# PR9018.net
KiCad netlist of a schematic drawn in EAGLE
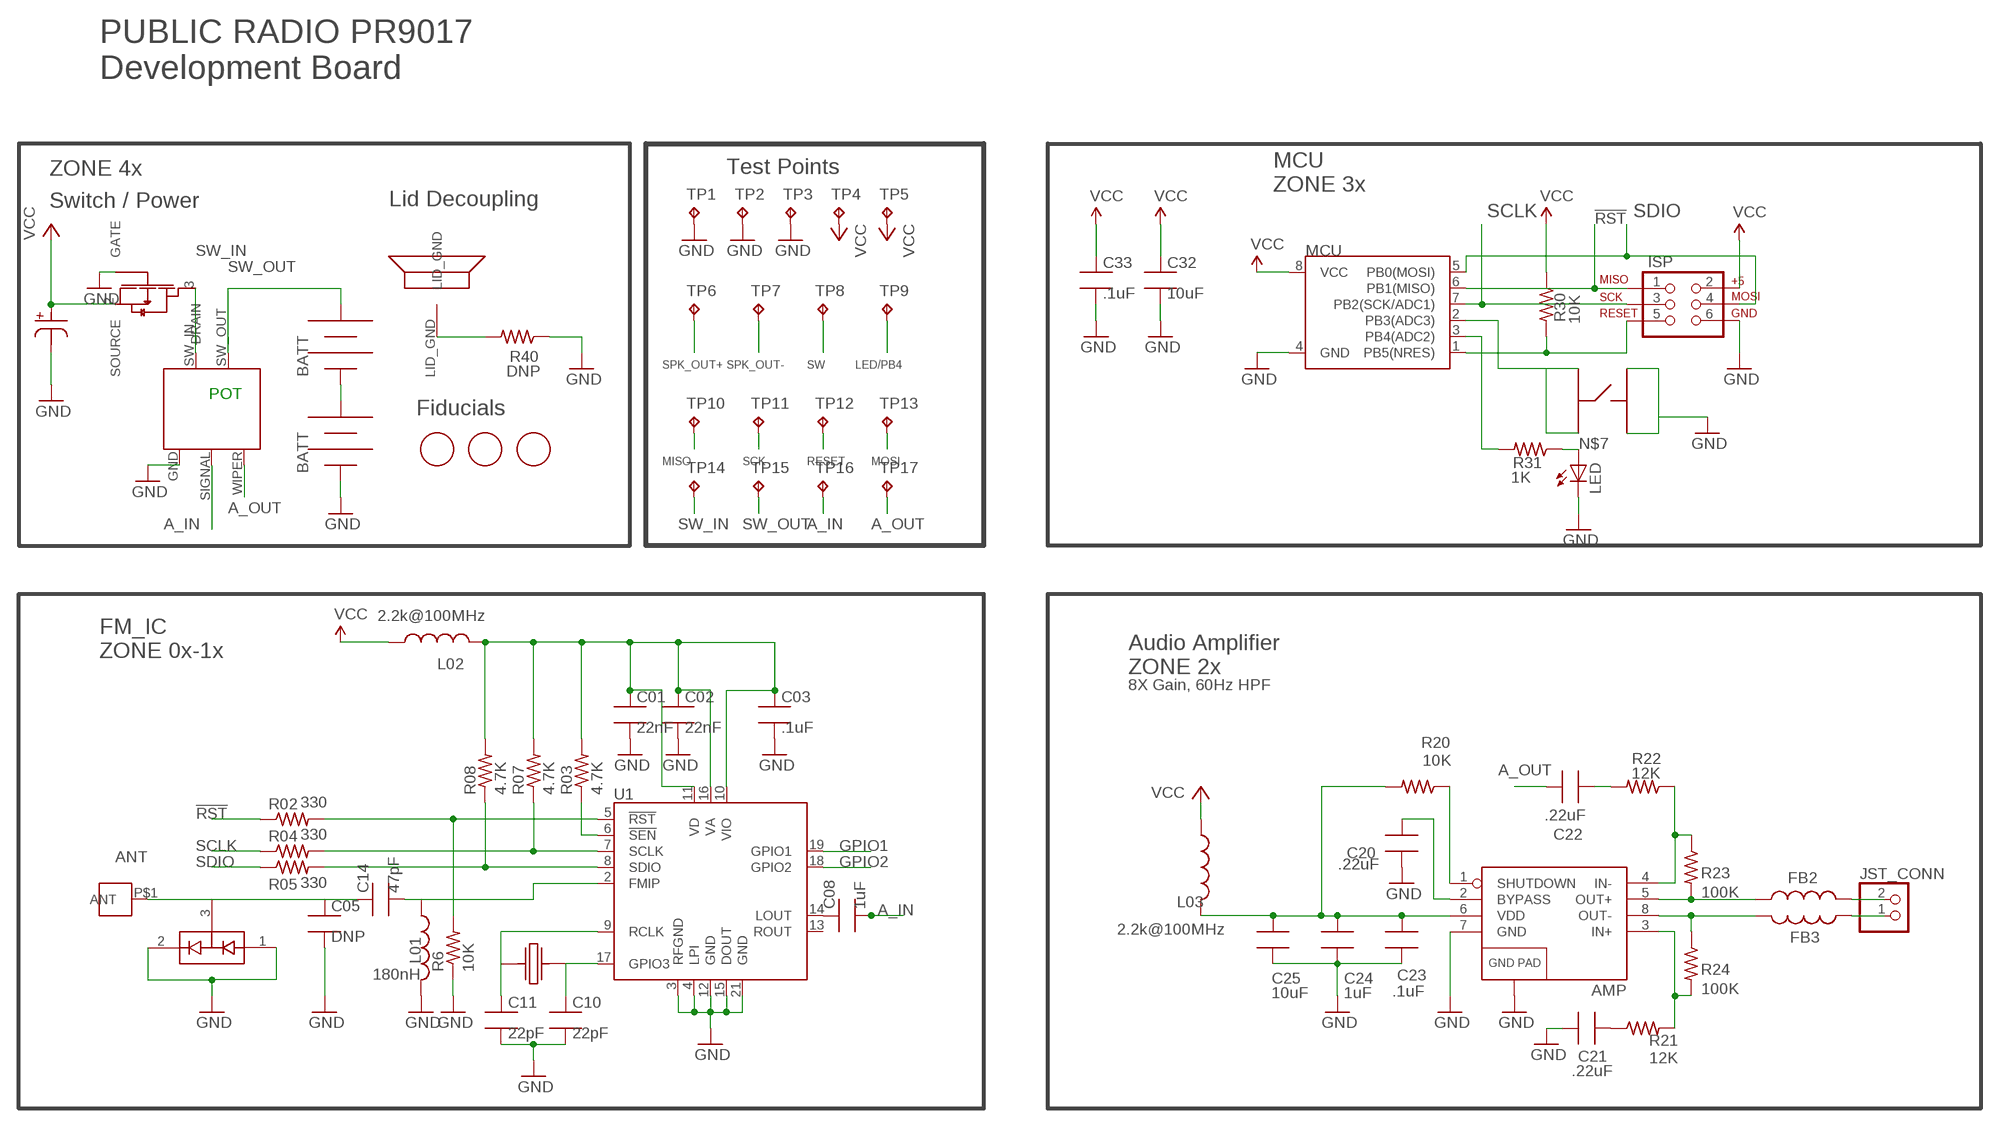
[diagram p0: schematic, sheet 1]

(export (version "E")
  (design (tool "Eeschema 10.0.6"))
  (components
    (comp (ref "AMP")
      (value "TPA6203A1")
      (footprint "eagle-import:8-MSOP")
      (libsource (lib "eagle-import") (part "TPA6203A1"))
    )
    (comp (ref "ANT_MOUNT")
      (value "DNP")
      (footprint "eagle-import:M3_BOLT_HOLE")
      (libsource (lib "eagle-import") (part "M3_SCREW_POST"))
    )
    (comp (ref "C01")
      (value "22nF")
      (footprint "eagle-import:0603_CPL")
      (fields
        (field (name "MFG_PN") "CL10B223KB8NNNC")
        (field (name "TOL") "10%")
        (field (name "VOLTAGE") "16V")
      )
      (libsource (lib "eagle-import") (part "C_SMT_0603_CPL"))
    )
    (comp (ref "C02")
      (value "22nF")
      (footprint "eagle-import:0603_CPL")
      (fields
        (field (name "MFG_PN") "CL10B223KB8NNNC")
        (field (name "TOL") "10%")
        (field (name "VOLTAGE") "16V")
      )
      (libsource (lib "eagle-import") (part "C_SMT_0603_CPL"))
    )
    (comp (ref "C03")
      (value ".1uF")
      (footprint "eagle-import:0603_CPL")
      (fields
        (field (name "MFG_PN") "CL10B104KB8SFNC")
        (field (name "TOL") "10%")
        (field (name "VOLTAGE") "16V")
      )
      (libsource (lib "eagle-import") (part "C_SMT_0603_CPL"))
    )
    (comp (ref "C05")
      (value "DNP")
      (footprint "eagle-import:0603_CPL")
      (fields (field (name "MFG_PN") "DNP") (field (name "TOL") "2%") (field (name "VOLTAGE") "50V"))
      (libsource (lib "eagle-import") (part "C_SMT_0603_CPL"))
    )
    (comp (ref "C08")
      (value "1uF")
      (footprint "eagle-import:0603_CPL")
      (fields
        (field (name "MFG_PN") "CL10B105KP8NNNC")
        (field (name "TOL") "10%")
        (field (name "VOLTAGE") "10V")
      )
      (libsource (lib "eagle-import") (part "C_SMT_0603_CPL"))
    )
    (comp (ref "C10")
      (value "22pF")
      (footprint "eagle-import:0603_CPL")
      (fields
        (field (name "MFG_PN") "C1608C0G1H220J080AA")
        (field (name "TOL") "5%")
        (field (name "VOLTAGE") "50V")
      )
      (libsource (lib "eagle-import") (part "C_SMT_0603_CPL"))
    )
    (comp (ref "C11")
      (value "22pF")
      (footprint "eagle-import:0603_CPL")
      (fields
        (field (name "MFG_PN") "C1608C0G1H220J080AA")
        (field (name "TOL") "5%")
        (field (name "VOLTAGE") "50V")
      )
      (libsource (lib "eagle-import") (part "C_SMT_0603_CPL"))
    )
    (comp (ref "C14")
      (value "47pF")
      (footprint "eagle-import:0603_CPL")
      (fields
        (field (name "MFG_PN") "CL10C470JB8NCNC")
        (field (name "TOL") "5%")
        (field (name "VOLTAGE") "50V")
      )
      (libsource (lib "eagle-import") (part "C_SMT_0603_CPL"))
    )
    (comp (ref "C20")
      (value ".22uF")
      (footprint "eagle-import:0603_CPL")
      (fields
        (field (name "MFG_PN") "C1608X7R1C224K080AC")
        (field (name "TOL") "10%")
        (field (name "VOLTAGE") "16V")
      )
      (libsource (lib "eagle-import") (part "C_SMT_0603_CPL"))
    )
    (comp (ref "C21")
      (value ".22uF")
      (footprint "eagle-import:0603_CPL")
      (fields
        (field (name "MFG_PN") "C1608X7R1C224K080AC")
        (field (name "TOL") "10%")
        (field (name "VOLTAGE") "16V")
      )
      (libsource (lib "eagle-import") (part "C_SMT_0603_CPL"))
    )
    (comp (ref "C22")
      (value ".22uF")
      (footprint "eagle-import:0603_CPL")
      (fields
        (field (name "MFG_PN") "C1608X7R1C224K080AC")
        (field (name "TOL") "10%")
        (field (name "VOLTAGE") "16V")
      )
      (libsource (lib "eagle-import") (part "C_SMT_0603_CPL"))
    )
    (comp (ref "C23")
      (value ".1uF")
      (footprint "eagle-import:0603_CPL")
      (fields
        (field (name "MFG_PN") "CL10B104KB8SFNC")
        (field (name "TOL") "10%")
        (field (name "VOLTAGE") "16V")
      )
      (libsource (lib "eagle-import") (part "C_SMT_0603_CPL"))
    )
    (comp (ref "C24")
      (value "1uF")
      (footprint "eagle-import:0603_CPL")
      (fields
        (field (name "MFG_PN") "CL10B105KP8NNNC")
        (field (name "TOL") "10%")
        (field (name "VOLTAGE") "10V")
      )
      (libsource (lib "eagle-import") (part "C_SMT_0603_CPL"))
    )
    (comp (ref "C25")
      (value "10uF")
      (footprint "eagle-import:0603_CPL")
      (fields
        (field (name "MFG_PN") "CL10A106MQ8NNNC")
        (field (name "TOL") "20%")
        (field (name "VOLTAGE") "6.3V")
      )
      (libsource (lib "eagle-import") (part "C_SMT_0603_CPL"))
    )
    (comp (ref "C32")
      (value "10uF")
      (footprint "eagle-import:0603_CPL")
      (fields
        (field (name "MFG_PN") "CL10A106MQ8NNNC")
        (field (name "TOL") "20%")
        (field (name "VOLTAGE") "6.3V")
      )
      (libsource (lib "eagle-import") (part "C_SMT_0603_CPL"))
    )
    (comp (ref "C33")
      (value ".1uF")
      (footprint "eagle-import:0603_CPL")
      (fields
        (field (name "MFG_PN") "CL10B104KB8SFNC")
        (field (name "TOL") "10%")
        (field (name "VOLTAGE") "16V")
      )
      (libsource (lib "eagle-import") (part "C_SMT_0603_CPL"))
    )
    (comp (ref "C40")
      (value "220uF")
      (footprint "eagle-import:NICHICON_UD_63")
      (fields (field (name "TOL") "20%") (field (name "VOLTAGE") "16V"))
      (libsource (lib "eagle-import") (part "NICHICON_SERIESUD"))
    )
    (comp (ref "D1")
      (value "BAV99")
      (footprint "eagle-import:SOT23_CPL")
      (fields (field (name "MFG_PN") "BAV99,215"))
      (libsource (lib "eagle-import") (part "BAV99"))
    )
    (comp (ref "FB2")
      (value "L_SMT_0805_ADAFRUIT")
      (footprint "eagle-import:0805_ADAFRUIT")
      (fields
        (field (name "CURRENT") "2A")
        (field (name "DCR") "45m")
        (field (name "MFG_PN") "HI0805R800R-10")
      )
      (libsource (lib "eagle-import") (part "L_SMT_0805_ADAFRUIT"))
    )
    (comp (ref "FB3")
      (value "L_SMT_0805_ADAFRUIT")
      (footprint "eagle-import:0805_ADAFRUIT")
      (fields
        (field (name "CURRENT") "2A")
        (field (name "DCR") "45m")
        (field (name "MFG_PN") "HI0805R800R-10")
      )
      (libsource (lib "eagle-import") (part "L_SMT_0805_ADAFRUIT"))
    )
    (comp (ref "FET1")
      (value "AO3435")
      (footprint "eagle-import:SOT23_CPL")
      (fields (field (name "MFG_PN") "AO3435"))
      (libsource (lib "eagle-import") (part "AO3435"))
    )
    (comp (ref "ISP")
      (value "AVR_SPI_PRG_6NS")
      (footprint "eagle-import:2X3-NS")
      (libsource (lib "eagle-import") (part "AVR_SPI_PRG_6NS"))
    )
    (comp (ref "JP5")
      (value "BK-92_MPD_AA_BATT_CLIP")
      (footprint "eagle-import:BK92_AA_BATT")
      (libsource (lib "eagle-import") (part "BK-92_MPD_AA_BATT_CLIP"))
    )
    (comp (ref "JP6")
      (value "BK-92_MPD_AA_BATT_CLIP")
      (footprint "eagle-import:BK92_AA_BATT")
      (libsource (lib "eagle-import") (part "BK-92_MPD_AA_BATT_CLIP"))
    )
    (comp (ref "JST_CONN")
      (value "JST_2PIN-SMT-RA")
      (footprint "eagle-import:JST-PH-2-SMT-RA")
      (libsource (lib "eagle-import") (part "JST_2PIN-SMT-RA"))
    )
    (comp (ref "L01")
      (value "180nH")
      (footprint "eagle-import:0805_ADAFRUIT")
      (fields
        (field (name "CURRENT") "400mA")
        (field (name "DCR") "640m")
        (field (name "MFG_PN") "AISC-0805-R18J-T")
        (field (name "TOL") "5%")
      )
      (libsource (lib "eagle-import") (part "L_SMT_0805_ADAFRUIT"))
    )
    (comp (ref "L02")
      (value "2.2k@100MHz")
      (footprint "eagle-import:0603_CPL")
      (fields
        (field (name "CURRENT") "150mA")
        (field (name "DCR") "2.3")
        (field (name "MFG_PN") "HZ0603A222R-10")
      )
      (libsource (lib "eagle-import") (part "L_SMT_0603_CPL"))
    )
    (comp (ref "L03")
      (value "2.2k@100MHz")
      (footprint "eagle-import:0603_CPL")
      (fields
        (field (name "CURRENT") "150mA")
        (field (name "DCR") "2.3")
        (field (name "MFG_PN") "HZ0603A222R-10")
      )
      (libsource (lib "eagle-import") (part "L_SMT_0603_CPL"))
    )
    (comp (ref "LED")
      (value "LED")
      (footprint "eagle-import:0603_CPL")
      (fields (field (name "MFG_PN") "LY R976-PS-36"))
      (libsource (lib "eagle-import") (part "LED"))
    )
    (comp (ref "MARK1")
      (value "FIDUCIAL")
      (footprint "eagle-import:FIDUCIAL_1MM")
      (libsource (lib "eagle-import") (part "FIDUCIAL"))
    )
    (comp (ref "MARK2")
      (value "FIDUCIAL")
      (footprint "eagle-import:FIDUCIAL_1MM")
      (libsource (lib "eagle-import") (part "FIDUCIAL"))
    )
    (comp (ref "MARK3")
      (value "FIDUCIAL")
      (footprint "eagle-import:FIDUCIAL_1MM")
      (libsource (lib "eagle-import") (part "FIDUCIAL"))
    )
    (comp (ref "MCU")
      (value "ATTINY45TINY45-20-SMT")
      (footprint "eagle-import:8-SOIC")
      (libsource (lib "eagle-import") (part "ATTINY45TINY45-20-SMT"))
    )
    (comp (ref "R1")
      (value "RV170SF_TAIWANA_POT_SW")
      (footprint "eagle-import:RV170SF_SW_POT")
      (libsource (lib "eagle-import") (part "RV170SF_TAIWANA_POT_SW"))
    )
    (comp (ref "R02")
      (value "330")
      (footprint "eagle-import:0603_CPL")
      (fields (field (name "MFG_PN") "MCR03ERTJ331") (field (name "POWER") "1/10W") (field (name "TOL") "5%"))
      (libsource (lib "eagle-import") (part "R_SMT_R0603_CPL"))
    )
    (comp (ref "R03")
      (value "4.7K")
      (footprint "eagle-import:0603_CPL")
      (fields
        (field (name "MFG_PN") "ERJ-3EKF4701V")
        (field (name "POWER") "1/10W")
        (field (name "TOL") "1%")
      )
      (libsource (lib "eagle-import") (part "R_SMT_R0603_CPL"))
    )
    (comp (ref "R04")
      (value "330")
      (footprint "eagle-import:0603_CPL")
      (fields (field (name "MFG_PN") "MCR03ERTJ331") (field (name "POWER") "1/10W") (field (name "TOL") "5%"))
      (libsource (lib "eagle-import") (part "R_SMT_R0603_CPL"))
    )
    (comp (ref "R05")
      (value "330")
      (footprint "eagle-import:0603_CPL")
      (fields (field (name "MFG_PN") "MCR03ERTJ331") (field (name "POWER") "1/10W") (field (name "TOL") "5%"))
      (libsource (lib "eagle-import") (part "R_SMT_R0603_CPL"))
    )
    (comp (ref "R6")
      (value "10K")
      (footprint "eagle-import:0603_CPL")
      (fields
        (field (name "MFG_PN") "ERJ-3GEYJ103V")
        (field (name "POWER") "1/10W")
        (field (name "TOL") "5%")
      )
      (libsource (lib "eagle-import") (part "R_SMT_R0603_CPL"))
    )
    (comp (ref "R07")
      (value "4.7K")
      (footprint "eagle-import:0603_CPL")
      (fields
        (field (name "MFG_PN") "ERJ-3EKF4701V")
        (field (name "POWER") "1/10W")
        (field (name "TOL") "1%")
      )
      (libsource (lib "eagle-import") (part "R_SMT_R0603_CPL"))
    )
    (comp (ref "R08")
      (value "4.7K")
      (footprint "eagle-import:0603_CPL")
      (fields
        (field (name "MFG_PN") "ERJ-3EKF4701V")
        (field (name "POWER") "1/10W")
        (field (name "TOL") "1%")
      )
      (libsource (lib "eagle-import") (part "R_SMT_R0603_CPL"))
    )
    (comp (ref "R20")
      (value "10K")
      (footprint "eagle-import:0603_CPL")
      (fields
        (field (name "MFG_PN") "ERJ-3GEYJ103V")
        (field (name "POWER") "1/10W")
        (field (name "TOL") "5%")
      )
      (libsource (lib "eagle-import") (part "R_SMT_R0603_CPL"))
    )
    (comp (ref "R21")
      (value "12K")
      (footprint "eagle-import:0603_CPL")
      (fields
        (field (name "MFG_PN") "RMCF0603FT12K0")
        (field (name "POWER") "1/10W")
        (field (name "TOL") "1%")
      )
      (libsource (lib "eagle-import") (part "R_SMT_R0603_CPL"))
    )
    (comp (ref "R22")
      (value "12K")
      (footprint "eagle-import:0603_CPL")
      (fields
        (field (name "MFG_PN") "RMCF0603FT12K0")
        (field (name "POWER") "1/10W")
        (field (name "TOL") "1%")
      )
      (libsource (lib "eagle-import") (part "R_SMT_R0603_CPL"))
    )
    (comp (ref "R23")
      (value "100K")
      (footprint "eagle-import:0603_CPL")
      (fields
        (field (name "MFG_PN") "RMCF0603FT100K")
        (field (name "POWER") "1/10W")
        (field (name "TOL") "1%")
      )
      (libsource (lib "eagle-import") (part "R_SMT_R0603_CPL"))
    )
    (comp (ref "R24")
      (value "100K")
      (footprint "eagle-import:0603_CPL")
      (fields
        (field (name "MFG_PN") "RMCF0603FT100K")
        (field (name "POWER") "1/10W")
        (field (name "TOL") "1%")
      )
      (libsource (lib "eagle-import") (part "R_SMT_R0603_CPL"))
    )
    (comp (ref "R30")
      (value "10K")
      (footprint "eagle-import:0603_CPL")
      (fields
        (field (name "MFG_PN") "ERJ-3GEYJ103V")
        (field (name "POWER") "1/10W")
        (field (name "TOL") "5%")
      )
      (libsource (lib "eagle-import") (part "R_SMT_R0603_CPL"))
    )
    (comp (ref "R31")
      (value "1K")
      (footprint "eagle-import:0603_CPL")
      (fields
        (field (name "MFG_PN") "ERJ-3EKF1001V")
        (field (name "POWER") "1/10W")
        (field (name "TOL") "1%")
      )
      (libsource (lib "eagle-import") (part "R_SMT_R0603_CPL"))
    )
    (comp (ref "R40")
      (value "DNP")
      (footprint "eagle-import:0603_CPL")
      (fields (field (name "MFG_PN") "ERJ-3GEY0R00V"))
      (libsource (lib "eagle-import") (part "R_SMT_R0603_CPL"))
    )
    (comp (ref "SPKR_PLACE")
      (value "DNP")
      (footprint "eagle-import:PR2023_SPKR_PLACE")
      (libsource (lib "eagle-import") (part "PR2023_SPKR"))
    )
    (comp (ref "SW1")
      (value "C&K_PTS645")
      (footprint "eagle-import:C&K_PTS645_SMT")
      (libsource (lib "eagle-import") (part "C&K_PTS645"))
    )
    (comp (ref "TP1")
      (value "TPTP20R")
      (footprint "eagle-import:TP20R")
      (libsource (lib "eagle-import") (part "TPTP20R"))
    )
    (comp (ref "TP2")
      (value "TPTP20R")
      (footprint "eagle-import:TP20R")
      (libsource (lib "eagle-import") (part "TPTP20R"))
    )
    (comp (ref "TP3")
      (value "TPTP20R")
      (footprint "eagle-import:TP20R")
      (libsource (lib "eagle-import") (part "TPTP20R"))
    )
    (comp (ref "TP4")
      (value "TPTP20R")
      (footprint "eagle-import:TP20R")
      (libsource (lib "eagle-import") (part "TPTP20R"))
    )
    (comp (ref "TP5")
      (value "TPTP20R")
      (footprint "eagle-import:TP20R")
      (libsource (lib "eagle-import") (part "TPTP20R"))
    )
    (comp (ref "TP6")
      (value "TPTP20R")
      (footprint "eagle-import:TP20R")
      (libsource (lib "eagle-import") (part "TPTP20R"))
    )
    (comp (ref "TP7")
      (value "TPTP20R")
      (footprint "eagle-import:TP20R")
      (libsource (lib "eagle-import") (part "TPTP20R"))
    )
    (comp (ref "TP8")
      (value "TPTP20R")
      (footprint "eagle-import:TP20R")
      (libsource (lib "eagle-import") (part "TPTP20R"))
    )
    (comp (ref "TP9")
      (value "TPTP20R")
      (footprint "eagle-import:TP20R")
      (libsource (lib "eagle-import") (part "TPTP20R"))
    )
    (comp (ref "TP10")
      (value "TPTP20R")
      (footprint "eagle-import:TP20R")
      (libsource (lib "eagle-import") (part "TPTP20R"))
    )
    (comp (ref "TP11")
      (value "TPTP20R")
      (footprint "eagle-import:TP20R")
      (libsource (lib "eagle-import") (part "TPTP20R"))
    )
    (comp (ref "TP12")
      (value "TPTP20R")
      (footprint "eagle-import:TP20R")
      (libsource (lib "eagle-import") (part "TPTP20R"))
    )
    (comp (ref "TP13")
      (value "TPTP20R")
      (footprint "eagle-import:TP20R")
      (libsource (lib "eagle-import") (part "TPTP20R"))
    )
    (comp (ref "TP14")
      (value "TPTP20R")
      (footprint "eagle-import:TP20R")
      (libsource (lib "eagle-import") (part "TPTP20R"))
    )
    (comp (ref "TP15")
      (value "TPTP20R")
      (footprint "eagle-import:TP20R")
      (libsource (lib "eagle-import") (part "TPTP20R"))
    )
    (comp (ref "TP16")
      (value "TPTP20R")
      (footprint "eagle-import:TP20R")
      (libsource (lib "eagle-import") (part "TPTP20R"))
    )
    (comp (ref "TP17")
      (value "TPTP20R")
      (footprint "eagle-import:TP20R")
      (libsource (lib "eagle-import") (part "TPTP20R"))
    )
    (comp (ref "U1")
      (value "SI4702-C19-GMR")
      (footprint "eagle-import:SI470X_20_QFN")
      (libsource (lib "eagle-import") (part "SI4702-C19-GMR"))
    )
    (comp (ref "X1")
      (value "ABS25XTAL")
      (footprint "eagle-import:4-SOJ")
      (libsource (lib "eagle-import") (part "ABS25XTAL"))
    )
  )
  (nets
    (net (code "1") (name "/ANT") (class "Default")
      (node (ref "ANT_MOUNT") (pin "P$1") (pinfunction "ANT_P$1") (pintype "bidirectional"))
      (node (ref "C05") (pin "1") (pinfunction "1_1") (pintype "passive"))
      (node (ref "C14") (pin "1") (pinfunction "1_1") (pintype "passive"))
      (node (ref "D1") (pin "3") (pinfunction "COM_3") (pintype "bidirectional"))
    )
    (net (code "2") (name "/A_IN") (class "Default")
      (node (ref "C08") (pin "2") (pinfunction "2_2") (pintype "passive"))
      (node (ref "R1") (pin "SIGNAL") (pinfunction "SIGNAL_SIGNAL") (pintype "bidirectional"))
      (node (ref "TP16") (pin "TP") (pinfunction "TP_TP") (pintype "input"))
    )
    (net (code "3") (name "/A_OUT") (class "Default")
      (node (ref "C22") (pin "2") (pinfunction "2_2") (pintype "passive"))
      (node (ref "R1") (pin "WIPER") (pinfunction "WIPER_WIPER") (pintype "bidirectional"))
      (node (ref "TP17") (pin "TP") (pinfunction "TP_TP") (pintype "input"))
    )
    (net (code "4") (name "/GPIO1") (class "Default")
      (node (ref "U1") (pin "19") (pinfunction "GPIO1_19") (pintype "bidirectional"))
    )
    (net (code "5") (name "/GPIO2") (class "Default")
      (node (ref "U1") (pin "18") (pinfunction "GPIO2_18") (pintype "bidirectional"))
    )
    (net (code "6") (name "/LED{slash}PB4") (class "Default")
      (node (ref "MCU") (pin "3") (pinfunction "PB4(ADC2)_3") (pintype "bidirectional"))
      (node (ref "R31") (pin "2") (pinfunction "2_2") (pintype "passive"))
      (node (ref "TP9") (pin "TP") (pinfunction "TP_TP") (pintype "input"))
    )
    (net (code "7") (name "/N$7") (class "Default")
      (node (ref "LED") (pin "1") (pinfunction "A_1") (pintype "passive"))
      (node (ref "R31") (pin "1") (pinfunction "1_1") (pintype "passive"))
    )
    (net (code "8") (name "/RESET") (class "Default")
      (node (ref "ISP") (pin "5") (pinfunction "5_5") (pintype "passive"))
      (node (ref "MCU") (pin "1") (pinfunction "PB5(NRES)_1") (pintype "bidirectional"))
      (node (ref "R30") (pin "2") (pinfunction "2_2") (pintype "passive"))
      (node (ref "TP12") (pin "TP") (pinfunction "TP_TP") (pintype "input"))
    )
    (net (code "9") (name "/SCLK") (class "Default")
      (node (ref "ISP") (pin "3") (pinfunction "3_3") (pintype "passive"))
      (node (ref "MCU") (pin "7") (pinfunction "PB2(SCK/ADC1)_7") (pintype "bidirectional"))
      (node (ref "R04") (pin "1") (pinfunction "1_1") (pintype "passive"))
      (node (ref "TP11") (pin "TP") (pinfunction "TP_TP") (pintype "input"))
    )
    (net (code "10") (name "/SDIO") (class "Default")
      (node (ref "ISP") (pin "4") (pinfunction "4_4") (pintype "passive"))
      (node (ref "MCU") (pin "5") (pinfunction "PB0(MOSI)_5") (pintype "bidirectional"))
      (node (ref "R05") (pin "1") (pinfunction "1_1") (pintype "passive"))
      (node (ref "TP13") (pin "TP") (pinfunction "TP_TP") (pintype "input"))
    )
    (net (code "11") (name "/SPK_OUT+") (class "Default")
      (node (ref "FB2") (pin "2") (pinfunction "2_2") (pintype "passive"))
      (node (ref "JST_CONN") (pin "2") (pinfunction "1_2") (pintype "passive"))
      (node (ref "TP6") (pin "TP") (pinfunction "TP_TP") (pintype "input"))
    )
    (net (code "12") (name "/SPK_OUT-") (class "Default")
      (node (ref "FB3") (pin "1") (pinfunction "1_1") (pintype "passive"))
      (node (ref "JST_CONN") (pin "1") (pinfunction "2_1") (pintype "passive"))
      (node (ref "TP7") (pin "TP") (pinfunction "TP_TP") (pintype "input"))
    )
    (net (code "13") (name "/SW") (class "Default")
      (node (ref "MCU") (pin "2") (pinfunction "PB3(ADC3)_2") (pintype "bidirectional"))
      (node (ref "SW1") (pin "P$3") (pinfunction "P$3_P$3") (pintype "bidirectional"))
      (node (ref "SW1") (pin "P$4") (pinfunction "P$4_P$4") (pintype "bidirectional"))
      (node (ref "TP8") (pin "TP") (pinfunction "TP_TP") (pintype "input"))
    )
    (net (code "14") (name "/SW_IN") (class "Default")
      (node (ref "FET1") (pin "3") (pinfunction "DRAIN_3") (pintype "bidirectional"))
      (node (ref "R1") (pin "SW_IN") (pinfunction "SW_IN_SW_IN") (pintype "bidirectional"))
      (node (ref "TP14") (pin "TP") (pinfunction "TP_TP") (pintype "input"))
    )
    (net (code "15") (name "/SW_OUT") (class "Default")
      (node (ref "JP5") (pin "POS") (pinfunction "POS_POS") (pintype "bidirectional"))
      (node (ref "JP5") (pin "POS@2") (pinfunction "POS_POS@2") (pintype "bidirectional"))
      (node (ref "R1") (pin "SW_OUT") (pinfunction "SW_OUT_SW_OUT") (pintype "bidirectional"))
      (node (ref "TP15") (pin "TP") (pinfunction "TP_TP") (pintype "input"))
    )
    (net (code "16") (name "/~{RST}") (class "Default")
      (node (ref "ISP") (pin "1") (pinfunction "1_1") (pintype "passive"))
      (node (ref "MCU") (pin "6") (pinfunction "PB1(MISO)_6") (pintype "bidirectional"))
      (node (ref "R02") (pin "1") (pinfunction "1_1") (pintype "passive"))
      (node (ref "TP10") (pin "TP") (pinfunction "TP_TP") (pintype "input"))
    )
    (net (code "17") (name "GND") (class "Default")
      (node (ref "AMP") (pin "7") (pinfunction "GND_7") (pintype "power_in"))
      (node (ref "AMP") (pin "9") (pinfunction "GND_9") (pintype "power_in"))
      (node (ref "C01") (pin "2") (pinfunction "2_2") (pintype "passive"))
      (node (ref "C02") (pin "2") (pinfunction "2_2") (pintype "passive"))
      (node (ref "C03") (pin "2") (pinfunction "2_2") (pintype "passive"))
      (node (ref "C05") (pin "2") (pinfunction "2_2") (pintype "passive"))
      (node (ref "C10") (pin "2") (pinfunction "2_2") (pintype "passive"))
      (node (ref "C11") (pin "2") (pinfunction "2_2") (pintype "passive"))
      (node (ref "C20") (pin "1") (pinfunction "1_1") (pintype "passive"))
      (node (ref "C21") (pin "1") (pinfunction "1_1") (pintype "passive"))
      (node (ref "C23") (pin "2") (pinfunction "2_2") (pintype "passive"))
      (node (ref "C24") (pin "2") (pinfunction "2_2") (pintype "passive"))
      (node (ref "C25") (pin "2") (pinfunction "2_2") (pintype "passive"))
      (node (ref "C32") (pin "2") (pinfunction "2_2") (pintype "passive"))
      (node (ref "C33") (pin "2") (pinfunction "2_2") (pintype "passive"))
      (node (ref "C40") (pin "P$2") (pinfunction "P$2_P$2") (pintype "bidirectional"))
      (node (ref "D1") (pin "1") (pinfunction "A1_1") (pintype "bidirectional"))
      (node (ref "D1") (pin "2") (pinfunction "C2_2") (pintype "bidirectional"))
      (node (ref "FET1") (pin "1") (pinfunction "GATE_1") (pintype "bidirectional"))
      (node (ref "ISP") (pin "6") (pinfunction "6_6") (pintype "passive"))
      (node (ref "JP6") (pin "NEG") (pinfunction "NEG_NEG") (pintype "bidirectional"))
      (node (ref "JP6") (pin "NEG@2") (pinfunction "NEG_NEG@2") (pintype "bidirectional"))
      (node (ref "L01") (pin "2") (pinfunction "2_2") (pintype "passive"))
      (node (ref "LED") (pin "2") (pinfunction "C_2") (pintype "passive"))
      (node (ref "MCU") (pin "4") (pinfunction "GND_4") (pintype "bidirectional"))
      (node (ref "R1") (pin "GND") (pinfunction "GND_GND") (pintype "bidirectional"))
      (node (ref "R40") (pin "1") (pinfunction "1_1") (pintype "passive"))
      (node (ref "R6") (pin "1") (pinfunction "1_1") (pintype "passive"))
      (node (ref "SW1") (pin "P$1") (pinfunction "P$1_P$1") (pintype "bidirectional"))
      (node (ref "SW1") (pin "P$2") (pinfunction "P$2_P$2") (pintype "bidirectional"))
      (node (ref "TP1") (pin "TP") (pinfunction "TP_TP") (pintype "input"))
      (node (ref "TP2") (pin "TP") (pinfunction "TP_TP") (pintype "input"))
      (node (ref "TP3") (pin "TP") (pinfunction "TP_TP") (pintype "input"))
      (node (ref "U1") (pin "12") (pinfunction "GND_12") (pintype "bidirectional"))
      (node (ref "U1") (pin "15") (pinfunction "DOUT_15") (pintype "bidirectional"))
      (node (ref "U1") (pin "21") (pinfunction "GND_21") (pintype "bidirectional"))
      (node (ref "U1") (pin "3") (pinfunction "RFGND_3") (pintype "bidirectional"))
      (node (ref "U1") (pin "4") (pinfunction "LPI_4") (pintype "bidirectional"))
    )
    (net (code "18") (name "Net-(AMP-BYPASS)") (class "Default")
      (node (ref "AMP") (pin "2") (pinfunction "BYPASS_2") (pintype "bidirectional"))
      (node (ref "C20") (pin "2") (pinfunction "2_2") (pintype "passive"))
    )
    (net (code "19") (name "Net-(AMP-IN+)") (class "Default")
      (node (ref "AMP") (pin "3") (pinfunction "IN+_3") (pintype "bidirectional"))
      (node (ref "R21") (pin "2") (pinfunction "2_2") (pintype "passive"))
      (node (ref "R24") (pin "2") (pinfunction "2_2") (pintype "passive"))
    )
    (net (code "20") (name "Net-(AMP-IN-)") (class "Default")
      (node (ref "AMP") (pin "4") (pinfunction "IN-_4") (pintype "bidirectional"))
      (node (ref "R22") (pin "1") (pinfunction "1_1") (pintype "passive"))
      (node (ref "R23") (pin "1") (pinfunction "1_1") (pintype "passive"))
    )
    (net (code "21") (name "Net-(AMP-OUT+)") (class "Default")
      (node (ref "AMP") (pin "5") (pinfunction "OUT+_5") (pintype "bidirectional"))
      (node (ref "FB2") (pin "1") (pinfunction "1_1") (pintype "passive"))
      (node (ref "R23") (pin "2") (pinfunction "2_2") (pintype "passive"))
    )
    (net (code "22") (name "Net-(AMP-OUT-)") (class "Default")
      (node (ref "AMP") (pin "8") (pinfunction "OUT-_8") (pintype "bidirectional"))
      (node (ref "FB3") (pin "2") (pinfunction "2_2") (pintype "passive"))
      (node (ref "R24") (pin "1") (pinfunction "1_1") (pintype "passive"))
    )
    (net (code "23") (name "Net-(AMP-SHUTDOWN)") (class "Default")
      (node (ref "AMP") (pin "1") (pinfunction "SHUTDOWN_1") (pintype "input"))
      (node (ref "R20") (pin "1") (pinfunction "1_1") (pintype "passive"))
    )
    (net (code "24") (name "Net-(AMP-VDD)") (class "Default")
      (node (ref "AMP") (pin "6") (pinfunction "VDD_6") (pintype "power_in"))
      (node (ref "C23") (pin "1") (pinfunction "1_1") (pintype "passive"))
      (node (ref "C24") (pin "1") (pinfunction "1_1") (pintype "passive"))
      (node (ref "C25") (pin "1") (pinfunction "1_1") (pintype "passive"))
      (node (ref "L03") (pin "2") (pinfunction "2_2") (pintype "passive"))
      (node (ref "R20") (pin "2") (pinfunction "2_2") (pintype "passive"))
    )
    (net (code "25") (name "Net-(C21-Pad2)") (class "Default")
      (node (ref "C21") (pin "2") (pinfunction "2_2") (pintype "passive"))
      (node (ref "R21") (pin "1") (pinfunction "1_1") (pintype "passive"))
    )
    (net (code "26") (name "Net-(C22-Pad1)") (class "Default")
      (node (ref "C22") (pin "1") (pinfunction "1_1") (pintype "passive"))
      (node (ref "R22") (pin "2") (pinfunction "2_2") (pintype "passive"))
    )
    (net (code "27") (name "Net-(JP5-NEG-PadNEG@2)") (class "Default")
      (node (ref "JP5") (pin "NEG") (pinfunction "NEG_NEG") (pintype "bidirectional"))
      (node (ref "JP5") (pin "NEG@2") (pinfunction "NEG_NEG@2") (pintype "bidirectional"))
      (node (ref "JP6") (pin "POS") (pinfunction "POS_POS") (pintype "bidirectional"))
      (node (ref "JP6") (pin "POS@2") (pinfunction "POS_POS@2") (pintype "bidirectional"))
    )
    (net (code "28") (name "Net-(R40-Pad2)") (class "Default")
      (node (ref "R40") (pin "2") (pinfunction "2_2") (pintype "passive"))
      (node (ref "SPKR_PLACE") (pin "LID_GND") (pinfunction "LID_GND_LID_GND") (pintype "bidirectional"))
    )
    (net (code "29") (name "Net-(U1-FMIP)") (class "Default")
      (node (ref "C14") (pin "2") (pinfunction "2_2") (pintype "passive"))
      (node (ref "L01") (pin "1") (pinfunction "1_1") (pintype "passive"))
      (node (ref "U1") (pin "2") (pinfunction "FMIP_2") (pintype "bidirectional"))
    )
    (net (code "30") (name "Net-(U1-GPIO3)") (class "Default")
      (node (ref "C10") (pin "1") (pinfunction "1_1") (pintype "passive"))
      (node (ref "U1") (pin "17") (pinfunction "GPIO3_17") (pintype "bidirectional"))
      (node (ref "X1") (pin "P$4") (pinfunction "P$4_P$4") (pintype "bidirectional"))
    )
    (net (code "31") (name "Net-(U1-LOUT)") (class "Default")
      (node (ref "C08") (pin "1") (pinfunction "1_1") (pintype "passive"))
      (node (ref "U1") (pin "14") (pinfunction "LOUT_14") (pintype "bidirectional"))
    )
    (net (code "32") (name "Net-(U1-RCLK)") (class "Default")
      (node (ref "C11") (pin "1") (pinfunction "1_1") (pintype "passive"))
      (node (ref "U1") (pin "9") (pinfunction "RCLK_9") (pintype "bidirectional"))
      (node (ref "X1") (pin "P$1") (pinfunction "P$1_P$1") (pintype "bidirectional"))
    )
    (net (code "33") (name "Net-(U1-SCLK)") (class "Default")
      (node (ref "R04") (pin "2") (pinfunction "2_2") (pintype "passive"))
      (node (ref "R07") (pin "1") (pinfunction "1_1") (pintype "passive"))
      (node (ref "U1") (pin "7") (pinfunction "SCLK_7") (pintype "bidirectional"))
    )
    (net (code "34") (name "Net-(U1-SDIO)") (class "Default")
      (node (ref "R05") (pin "2") (pinfunction "2_2") (pintype "passive"))
      (node (ref "R08") (pin "1") (pinfunction "1_1") (pintype "passive"))
      (node (ref "U1") (pin "8") (pinfunction "SDIO_8") (pintype "bidirectional"))
    )
    (net (code "35") (name "Net-(U1-VA)") (class "Default")
      (node (ref "C01") (pin "1") (pinfunction "1_1") (pintype "passive"))
      (node (ref "C02") (pin "1") (pinfunction "1_1") (pintype "passive"))
      (node (ref "C03") (pin "1") (pinfunction "1_1") (pintype "passive"))
      (node (ref "L02") (pin "2") (pinfunction "2_2") (pintype "passive"))
      (node (ref "R03") (pin "2") (pinfunction "2_2") (pintype "passive"))
      (node (ref "R07") (pin "2") (pinfunction "2_2") (pintype "passive"))
      (node (ref "R08") (pin "2") (pinfunction "2_2") (pintype "passive"))
      (node (ref "U1") (pin "10") (pinfunction "VIO_10") (pintype "bidirectional"))
      (node (ref "U1") (pin "11") (pinfunction "VD_11") (pintype "bidirectional"))
      (node (ref "U1") (pin "16") (pinfunction "VA_16") (pintype "bidirectional"))
    )
    (net (code "36") (name "Net-(U1-~{RST})") (class "Default")
      (node (ref "R02") (pin "2") (pinfunction "2_2") (pintype "passive"))
      (node (ref "R6") (pin "2") (pinfunction "2_2") (pintype "passive"))
      (node (ref "U1") (pin "5") (pinfunction "~{RST}_5") (pintype "bidirectional"))
    )
    (net (code "37") (name "Net-(U1-~{SEN})") (class "Default")
      (node (ref "R03") (pin "1") (pinfunction "1_1") (pintype "passive"))
      (node (ref "U1") (pin "6") (pinfunction "~{SEN}_6") (pintype "bidirectional"))
    )
    (net (code "38") (name "VCC") (class "Default")
      (node (ref "C32") (pin "1") (pinfunction "1_1") (pintype "passive"))
      (node (ref "C33") (pin "1") (pinfunction "1_1") (pintype "passive"))
      (node (ref "C40") (pin "P$1") (pinfunction "P$1_P$1") (pintype "bidirectional"))
      (node (ref "FET1") (pin "2") (pinfunction "SOURCE_2") (pintype "bidirectional"))
      (node (ref "ISP") (pin "2") (pinfunction "2_2") (pintype "passive"))
      (node (ref "L02") (pin "1") (pinfunction "1_1") (pintype "passive"))
      (node (ref "L03") (pin "1") (pinfunction "1_1") (pintype "passive"))
      (node (ref "MCU") (pin "8") (pinfunction "VCC_8") (pintype "bidirectional"))
      (node (ref "R30") (pin "1") (pinfunction "1_1") (pintype "passive"))
      (node (ref "TP4") (pin "TP") (pinfunction "TP_TP") (pintype "input"))
      (node (ref "TP5") (pin "TP") (pinfunction "TP_TP") (pintype "input"))
    )
    (net (code "39") (name "unconnected-(U1-ROUT-Pad13)") (class "Default")
      (node (ref "U1") (pin "13") (pinfunction "ROUT_13") (pintype "bidirectional"))
    )
  )
)
